# schematic_usb_multirs232.net
KiCad netlist of a schematic drawn in Altium Designer
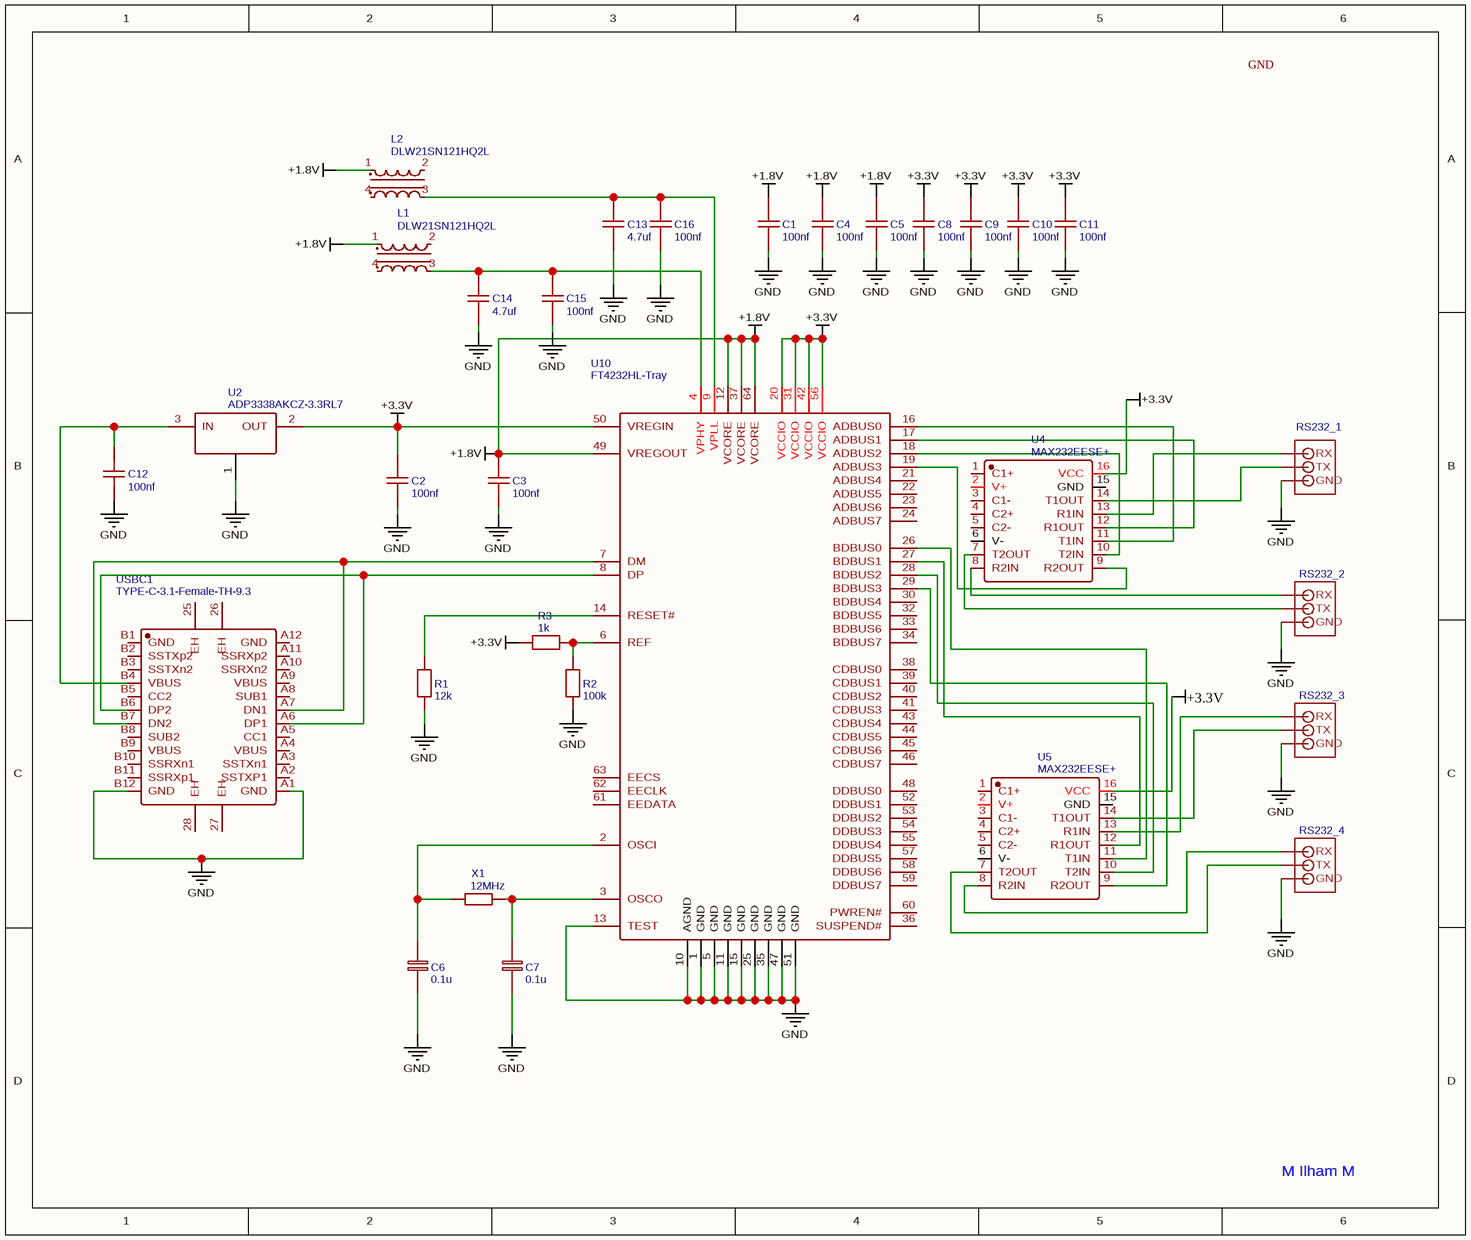
[diagram p0: schematic_usb_multirs232.schdoc]

(export (version "E")
  (design (tool "Eeschema 10.0.6"))
  (components
    (comp (ref "C1")
      (value "100nf")
      (fields (field (name "CONTRIBUTOR") "LCEDA_Lib"))
      (libsource (lib "altium-import") (part "root_3_100nf_"))
    )
    (comp (ref "C2")
      (value "100nf")
      (fields (field (name "CONTRIBUTOR") "LCEDA_Lib"))
      (libsource (lib "altium-import") (part "root_3_100nf_"))
    )
    (comp (ref "C3")
      (value "100nf")
      (fields (field (name "CONTRIBUTOR") "LCEDA_Lib"))
      (libsource (lib "altium-import") (part "root_3_100nf_"))
    )
    (comp (ref "C4")
      (value "100nf")
      (fields (field (name "CONTRIBUTOR") "LCEDA_Lib"))
      (libsource (lib "altium-import") (part "root_3_100nf_"))
    )
    (comp (ref "C5")
      (value "100nf")
      (fields (field (name "CONTRIBUTOR") "LCEDA_Lib"))
      (libsource (lib "altium-import") (part "root_3_100nf_"))
    )
    (comp (ref "C6")
      (value "0.1u")
      (fields (field (name "CONTRIBUTOR") "LCEDA_Lib"))
      (libsource (lib "altium-import") (part "root_3_0.1u_"))
    )
    (comp (ref "C7")
      (value "0.1u")
      (fields (field (name "CONTRIBUTOR") "LCEDA_Lib"))
      (libsource (lib "altium-import") (part "root_3_0.1u_"))
    )
    (comp (ref "C8")
      (value "100nf")
      (fields (field (name "CONTRIBUTOR") "LCEDA_Lib"))
      (libsource (lib "altium-import") (part "root_3_100nf_"))
    )
    (comp (ref "C9")
      (value "100nf")
      (fields (field (name "CONTRIBUTOR") "LCEDA_Lib"))
      (libsource (lib "altium-import") (part "root_3_100nf_"))
    )
    (comp (ref "C10")
      (value "100nf")
      (fields (field (name "CONTRIBUTOR") "LCEDA_Lib"))
      (libsource (lib "altium-import") (part "root_3_100nf_"))
    )
    (comp (ref "C11")
      (value "100nf")
      (fields (field (name "CONTRIBUTOR") "LCEDA_Lib"))
      (libsource (lib "altium-import") (part "root_3_100nf_"))
    )
    (comp (ref "C12")
      (value "100nf")
      (fields (field (name "CONTRIBUTOR") "LCEDA_Lib"))
      (libsource (lib "altium-import") (part "root_3_100nf_"))
    )
    (comp (ref "C13")
      (value "4.7uf")
      (fields (field (name "CONTRIBUTOR") "LCEDA_Lib"))
      (libsource (lib "altium-import") (part "root_3_4.7uf_"))
    )
    (comp (ref "C14")
      (value "4.7uf")
      (fields (field (name "CONTRIBUTOR") "LCEDA_Lib"))
      (libsource (lib "altium-import") (part "root_3_4.7uf_"))
    )
    (comp (ref "C15")
      (value "100nf")
      (fields (field (name "CONTRIBUTOR") "LCEDA_Lib"))
      (libsource (lib "altium-import") (part "root_3_100nf_"))
    )
    (comp (ref "C16")
      (value "100nf")
      (fields (field (name "CONTRIBUTOR") "LCEDA_Lib"))
      (libsource (lib "altium-import") (part "root_3_100nf_"))
    )
    (comp (ref "L1")
      (value "DLW21SN121HQ2L")
      (fields (field (name "MANUFACTURER") "muRata(村田)") (field (name "CONTRIBUTOR") "LCSC"))
      (libsource (lib "altium-import") (part "root_0_DLW21SN121HQ2L_"))
    )
    (comp (ref "L2")
      (value "DLW21SN121HQ2L")
      (fields (field (name "MANUFACTURER") "muRata(村田)") (field (name "CONTRIBUTOR") "LCSC"))
      (libsource (lib "altium-import") (part "root_0_DLW21SN121HQ2L_"))
    )
    (comp (ref "R1")
      (value "12k")
      (fields (field (name "CONTRIBUTOR") "LCEDA_Lib"))
      (libsource (lib "altium-import") (part "root_3_12k_"))
    )
    (comp (ref "R2")
      (value "100k")
      (fields (field (name "CONTRIBUTOR") "LCEDA_Lib"))
      (libsource (lib "altium-import") (part "root_3_100k_"))
    )
    (comp (ref "R3")
      (value "1k")
      (fields (field (name "CONTRIBUTOR") "LCEDA_Lib"))
      (libsource (lib "altium-import") (part "root_0_1k_"))
    )
    (comp (ref "RS232_1") (value "RX") (libsource (lib "altium-import") (part "root_0_RX_")))
    (comp (ref "U2")
      (value "ADP3338AKCZ-3.3RL7")
      (libsource (lib "altium-import") (part "root_0_ADP3338AKCZ-3.3RL7_"))
    )
    (comp (ref "U4")
      (value "MAX232EESE+")
      (fields (field (name "MANUFACTURER") "ADI(亚德诺)/MAXIM(美信)") (field (name "CONTRIBUTOR") "lcsc"))
      (libsource (lib "altium-import") (part "root_0_MAX232EESE+_"))
    )
    (comp (ref "U5")
      (value "MAX232EESE+")
      (fields (field (name "MANUFACTURER") "ADI(亚德诺)/MAXIM(美信)") (field (name "CONTRIBUTOR") "lcsc"))
      (libsource (lib "altium-import") (part "root_0_MAX232EESE+_"))
    )
    (comp (ref "U7") (value "RS232_2") (libsource (lib "altium-import") (part "root_0_RS232_2_")))
    (comp (ref "U8") (value "RS232_3") (libsource (lib "altium-import") (part "root_0_RS232_3_")))
    (comp (ref "U9") (value "RS232_4") (libsource (lib "altium-import") (part "root_0_RS232_4_")))
    (comp (ref "U10")
      (value "FT4232HL-Tray")
      (description "Quad High Speed USB To Multipurpose UARTMPSSE IC, 64-pin LQFP, Tray")
      (libsource (lib "altium-import") (part "root_0_FT4232HL-Tray_"))
    )
    (comp (ref "USBC1")
      (value "TYPE-C-3.1-Female-TH-9.3")
      (fields
        (field (name "MANUFACTURER") "精拓金")
        (field (name "MANUFACTURER PART") "918-418K2022Y40004")
        (field (name "CONTRIBUTOR") "LCSC")
      )
      (libsource (lib "altium-import") (part "root_0_TYPE-C-3.1-Female-TH-9.3_"))
    )
    (comp (ref "X1")
      (value "12MHz")
      (fields
        (field (name "MANUFACTURER") "CTS(西迪斯)")
        (field (name "MANUFACTURER PART") "ATS240CSM-1E")
        (field (name "CONTRIBUTOR") "LCSC")
      )
      (libsource (lib "altium-import") (part "root_0_12MHz_"))
    )
  )
  (nets
    (net (code "1") (name "+1.8V") (class "Default")
      (node (ref "C1") (pin "1") (pinfunction "1_1") (pintype "passive"))
      (node (ref "C3") (pin "1") (pinfunction "1_1") (pintype "passive"))
      (node (ref "C4") (pin "1") (pinfunction "1_1") (pintype "passive"))
      (node (ref "C5") (pin "1") (pinfunction "1_1") (pintype "passive"))
      (node (ref "L1") (pin "1") (pinfunction "1_1") (pintype "passive"))
      (node (ref "L2") (pin "1") (pinfunction "1_1") (pintype "passive"))
      (node (ref "U10") (pin "12") (pinfunction "VCORE_12") (pintype "passive"))
      (node (ref "U10") (pin "37") (pinfunction "VCORE_37") (pintype "passive"))
      (node (ref "U10") (pin "49") (pinfunction "VREGOUT_49") (pintype "passive"))
      (node (ref "U10") (pin "64") (pinfunction "VCORE_64") (pintype "passive"))
      (node (ref "U5") (pin "16") (pinfunction "VCC_16") (pintype "passive"))
    )
    (net (code "2") (name "+3.3V") (class "Default")
      (node (ref "C10") (pin "1") (pinfunction "1_1") (pintype "passive"))
      (node (ref "C11") (pin "1") (pinfunction "1_1") (pintype "passive"))
      (node (ref "C2") (pin "1") (pinfunction "1_1") (pintype "passive"))
      (node (ref "C8") (pin "1") (pinfunction "1_1") (pintype "passive"))
      (node (ref "C9") (pin "1") (pinfunction "1_1") (pintype "passive"))
      (node (ref "R3") (pin "1") (pinfunction "1_1") (pintype "passive"))
      (node (ref "U10") (pin "20") (pinfunction "VCCIO_20") (pintype "passive"))
      (node (ref "U10") (pin "31") (pinfunction "VCCIO_31") (pintype "passive"))
      (node (ref "U10") (pin "42") (pinfunction "VCCIO_42") (pintype "passive"))
      (node (ref "U10") (pin "50") (pinfunction "VREGIN_50") (pintype "passive"))
      (node (ref "U10") (pin "56") (pinfunction "VCCIO_56") (pintype "passive"))
      (node (ref "U2") (pin "2") (pinfunction "OUT_2") (pintype "passive"))
      (node (ref "U4") (pin "16") (pinfunction "VCC_16") (pintype "passive"))
    )
    (net (code "3") (name "GND") (class "Default")
      (node (ref "C1") (pin "2") (pinfunction "2_2") (pintype "passive"))
      (node (ref "C10") (pin "2") (pinfunction "2_2") (pintype "passive"))
      (node (ref "C11") (pin "2") (pinfunction "2_2") (pintype "passive"))
      (node (ref "C12") (pin "2") (pinfunction "2_2") (pintype "passive"))
      (node (ref "C13") (pin "2") (pinfunction "2_2") (pintype "passive"))
      (node (ref "C14") (pin "2") (pinfunction "2_2") (pintype "passive"))
      (node (ref "C15") (pin "2") (pinfunction "2_2") (pintype "passive"))
      (node (ref "C16") (pin "2") (pinfunction "2_2") (pintype "passive"))
      (node (ref "C2") (pin "2") (pinfunction "2_2") (pintype "passive"))
      (node (ref "C3") (pin "2") (pinfunction "2_2") (pintype "passive"))
      (node (ref "C4") (pin "2") (pinfunction "2_2") (pintype "passive"))
      (node (ref "C5") (pin "2") (pinfunction "2_2") (pintype "passive"))
      (node (ref "C6") (pin "2") (pinfunction "2_2") (pintype "passive"))
      (node (ref "C7") (pin "2") (pinfunction "2_2") (pintype "passive"))
      (node (ref "C8") (pin "2") (pinfunction "2_2") (pintype "passive"))
      (node (ref "C9") (pin "2") (pinfunction "2_2") (pintype "passive"))
      (node (ref "R1") (pin "2") (pinfunction "2_2") (pintype "passive"))
      (node (ref "R2") (pin "2") (pinfunction "2_2") (pintype "passive"))
      (node (ref "RS232_1") (pin "P3") (pinfunction "GND_P3") (pintype "passive"))
      (node (ref "U10") (pin "1") (pinfunction "GND_1") (pintype "passive"))
      (node (ref "U10") (pin "10") (pinfunction "AGND_10") (pintype "passive"))
      (node (ref "U10") (pin "11") (pinfunction "GND_11") (pintype "passive"))
      (node (ref "U10") (pin "13") (pinfunction "TEST_13") (pintype "passive"))
      (node (ref "U10") (pin "15") (pinfunction "GND_15") (pintype "passive"))
      (node (ref "U10") (pin "25") (pinfunction "GND_25") (pintype "passive"))
      (node (ref "U10") (pin "35") (pinfunction "GND_35") (pintype "passive"))
      (node (ref "U10") (pin "47") (pinfunction "GND_47") (pintype "passive"))
      (node (ref "U10") (pin "5") (pinfunction "GND_5") (pintype "passive"))
      (node (ref "U10") (pin "51") (pinfunction "GND_51") (pintype "passive"))
      (node (ref "U2") (pin "1") (pinfunction "GND_1") (pintype "passive"))
      (node (ref "U7") (pin "P3") (pinfunction "GND_P3") (pintype "passive"))
      (node (ref "U8") (pin "P3") (pinfunction "GND_P3") (pintype "passive"))
      (node (ref "U9") (pin "P3") (pinfunction "GND_P3") (pintype "passive"))
      (node (ref "USBC1") (pin "A1") (pinfunction "GND_A1") (pintype "passive"))
      (node (ref "USBC1") (pin "B12") (pinfunction "GND_B12") (pintype "passive"))
    )
    (net (code "4") (name "Net-(RS232_1-RX)") (class "Default")
      (node (ref "RS232_1") (pin "P1") (pinfunction "RX_P1") (pintype "passive"))
      (node (ref "U4") (pin "13") (pinfunction "R1IN_13") (pintype "passive"))
    )
    (net (code "5") (name "Net-(RS232_1-TX)") (class "Default")
      (node (ref "RS232_1") (pin "P2") (pinfunction "TX_P2") (pintype "passive"))
      (node (ref "U4") (pin "14") (pinfunction "T1OUT_14") (pintype "passive"))
    )
    (net (code "6") (name "Net-(U2-IN)") (class "Default")
      (node (ref "C12") (pin "1") (pinfunction "1_1") (pintype "passive"))
      (node (ref "U2") (pin "3") (pinfunction "IN_3") (pintype "passive"))
      (node (ref "USBC1") (pin "B4") (pinfunction "VBUS_B4") (pintype "passive"))
    )
    (net (code "7") (name "Net-(U4-R2IN)") (class "Default")
      (node (ref "U4") (pin "8") (pinfunction "R2IN_8") (pintype "passive"))
      (node (ref "U7") (pin "P1") (pinfunction "RX_P1") (pintype "passive"))
    )
    (net (code "8") (name "Net-(U4-T2OUT)") (class "Default")
      (node (ref "U4") (pin "7") (pinfunction "T2OUT_7") (pintype "passive"))
      (node (ref "U7") (pin "P2") (pinfunction "TX_P2") (pintype "passive"))
    )
    (net (code "9") (name "Net-(U5-R1IN)") (class "Default")
      (node (ref "U5") (pin "13") (pinfunction "R1IN_13") (pintype "passive"))
      (node (ref "U8") (pin "P1") (pinfunction "RX_P1") (pintype "passive"))
    )
    (net (code "10") (name "Net-(U5-R2IN)") (class "Default")
      (node (ref "U5") (pin "8") (pinfunction "R2IN_8") (pintype "passive"))
      (node (ref "U9") (pin "P1") (pinfunction "RX_P1") (pintype "passive"))
    )
    (net (code "11") (name "Net-(U5-T1OUT)") (class "Default")
      (node (ref "U5") (pin "14") (pinfunction "T1OUT_14") (pintype "passive"))
      (node (ref "U8") (pin "P2") (pinfunction "TX_P2") (pintype "passive"))
    )
    (net (code "12") (name "Net-(U5-T2OUT)") (class "Default")
      (node (ref "U5") (pin "7") (pinfunction "T2OUT_7") (pintype "passive"))
      (node (ref "U9") (pin "P2") (pinfunction "TX_P2") (pintype "passive"))
    )
    (net (code "13") (name "Net-(U10-ADBUS0)") (class "Default")
      (node (ref "U10") (pin "16") (pinfunction "ADBUS0_16") (pintype "passive"))
      (node (ref "U4") (pin "11") (pinfunction "T1IN_11") (pintype "passive"))
    )
    (net (code "14") (name "Net-(U10-ADBUS1)") (class "Default")
      (node (ref "U10") (pin "17") (pinfunction "ADBUS1_17") (pintype "passive"))
      (node (ref "U4") (pin "12") (pinfunction "R1OUT_12") (pintype "passive"))
    )
    (net (code "15") (name "Net-(U10-ADBUS2)") (class "Default")
      (node (ref "U10") (pin "18") (pinfunction "ADBUS2_18") (pintype "passive"))
      (node (ref "U4") (pin "10") (pinfunction "T2IN_10") (pintype "passive"))
    )
    (net (code "16") (name "Net-(U10-ADBUS3)") (class "Default")
      (node (ref "U10") (pin "19") (pinfunction "ADBUS3_19") (pintype "passive"))
      (node (ref "U4") (pin "9") (pinfunction "R2OUT_9") (pintype "passive"))
    )
    (net (code "17") (name "Net-(U10-BDBUS0)") (class "Default")
      (node (ref "U10") (pin "26") (pinfunction "BDBUS0_26") (pintype "passive"))
      (node (ref "U5") (pin "11") (pinfunction "T1IN_11") (pintype "passive"))
    )
    (net (code "18") (name "Net-(U10-BDBUS1)") (class "Default")
      (node (ref "U10") (pin "27") (pinfunction "BDBUS1_27") (pintype "passive"))
      (node (ref "U5") (pin "12") (pinfunction "R1OUT_12") (pintype "passive"))
    )
    (net (code "19") (name "Net-(U10-BDBUS2)") (class "Default")
      (node (ref "U10") (pin "28") (pinfunction "BDBUS2_28") (pintype "passive"))
      (node (ref "U5") (pin "10") (pinfunction "T2IN_10") (pintype "passive"))
    )
    (net (code "20") (name "Net-(U10-BDBUS3)") (class "Default")
      (node (ref "U10") (pin "29") (pinfunction "BDBUS3_29") (pintype "passive"))
      (node (ref "U5") (pin "9") (pinfunction "R2OUT_9") (pintype "passive"))
    )
    (net (code "21") (name "Net-(U10-DM)") (class "Default")
      (node (ref "U10") (pin "7") (pinfunction "DM_7") (pintype "passive"))
      (node (ref "USBC1") (pin "A7") (pinfunction "DN1_A7") (pintype "passive"))
      (node (ref "USBC1") (pin "B7") (pinfunction "DN2_B7") (pintype "passive"))
    )
    (net (code "22") (name "Net-(U10-DP)") (class "Default")
      (node (ref "U10") (pin "8") (pinfunction "DP_8") (pintype "passive"))
      (node (ref "USBC1") (pin "A6") (pinfunction "DP1_A6") (pintype "passive"))
      (node (ref "USBC1") (pin "B6") (pinfunction "DP2_B6") (pintype "passive"))
    )
    (net (code "23") (name "Net-(U10-OSCI)") (class "Default")
      (node (ref "C6") (pin "1") (pinfunction "1_1") (pintype "passive"))
      (node (ref "U10") (pin "2") (pinfunction "OSCI_2") (pintype "passive"))
      (node (ref "X1") (pin "1") (pinfunction "1_1") (pintype "passive"))
    )
    (net (code "24") (name "Net-(U10-OSCO)") (class "Default")
      (node (ref "C7") (pin "1") (pinfunction "1_1") (pintype "passive"))
      (node (ref "U10") (pin "3") (pinfunction "OSCO_3") (pintype "passive"))
      (node (ref "X1") (pin "2") (pinfunction "2_2") (pintype "passive"))
    )
    (net (code "25") (name "Net-(U10-REF)") (class "Default")
      (node (ref "R2") (pin "1") (pinfunction "1_1") (pintype "passive"))
      (node (ref "R3") (pin "2") (pinfunction "2_2") (pintype "passive"))
      (node (ref "U10") (pin "6") (pinfunction "REF_6") (pintype "passive"))
    )
    (net (code "26") (name "Net-(U10-RESET#)") (class "Default")
      (node (ref "R1") (pin "1") (pinfunction "1_1") (pintype "passive"))
      (node (ref "U10") (pin "14") (pinfunction "RESET#_14") (pintype "passive"))
    )
    (net (code "27") (name "Net-(U10-VPHY)") (class "Default")
      (node (ref "C14") (pin "1") (pinfunction "1_1") (pintype "passive"))
      (node (ref "C15") (pin "1") (pinfunction "1_1") (pintype "passive"))
      (node (ref "L1") (pin "3") (pinfunction "3_3") (pintype "passive"))
      (node (ref "U10") (pin "4") (pinfunction "VPHY_4") (pintype "passive"))
    )
    (net (code "28") (name "Net-(U10-VPLL)") (class "Default")
      (node (ref "C13") (pin "1") (pinfunction "1_1") (pintype "passive"))
      (node (ref "C16") (pin "1") (pinfunction "1_1") (pintype "passive"))
      (node (ref "L2") (pin "3") (pinfunction "3_3") (pintype "passive"))
      (node (ref "U10") (pin "9") (pinfunction "VPLL_9") (pintype "passive"))
    )
    (net (code "29") (name "unconnected-(L1-Pad2)") (class "Default")
      (node (ref "L1") (pin "2") (pinfunction "2_2") (pintype "passive"))
    )
    (net (code "30") (name "unconnected-(L1-Pad4)") (class "Default")
      (node (ref "L1") (pin "4") (pinfunction "4_4") (pintype "passive"))
    )
    (net (code "31") (name "unconnected-(L2-Pad2)") (class "Default")
      (node (ref "L2") (pin "2") (pinfunction "2_2") (pintype "passive"))
    )
    (net (code "32") (name "unconnected-(L2-Pad4)") (class "Default")
      (node (ref "L2") (pin "4") (pinfunction "4_4") (pintype "passive"))
    )
    (net (code "33") (name "unconnected-(U4-C1+-Pad1)") (class "Default")
      (node (ref "U4") (pin "1") (pinfunction "C1+_1") (pintype "passive"))
    )
    (net (code "34") (name "unconnected-(U4-C1--Pad3)") (class "Default")
      (node (ref "U4") (pin "3") (pinfunction "C1-_3") (pintype "passive"))
    )
    (net (code "35") (name "unconnected-(U4-C2+-Pad4)") (class "Default")
      (node (ref "U4") (pin "4") (pinfunction "C2+_4") (pintype "passive"))
    )
    (net (code "36") (name "unconnected-(U4-C2--Pad5)") (class "Default")
      (node (ref "U4") (pin "5") (pinfunction "C2-_5") (pintype "passive"))
    )
    (net (code "37") (name "unconnected-(U4-GND-Pad15)") (class "Default")
      (node (ref "U4") (pin "15") (pinfunction "GND_15") (pintype "passive"))
    )
    (net (code "38") (name "unconnected-(U4-V+-Pad2)") (class "Default")
      (node (ref "U4") (pin "2") (pinfunction "V+_2") (pintype "passive"))
    )
    (net (code "39") (name "unconnected-(U4-V--Pad6)") (class "Default")
      (node (ref "U4") (pin "6") (pinfunction "V-_6") (pintype "passive"))
    )
    (net (code "40") (name "unconnected-(U5-C1+-Pad1)") (class "Default")
      (node (ref "U5") (pin "1") (pinfunction "C1+_1") (pintype "passive"))
    )
    (net (code "41") (name "unconnected-(U5-C1--Pad3)") (class "Default")
      (node (ref "U5") (pin "3") (pinfunction "C1-_3") (pintype "passive"))
    )
    (net (code "42") (name "unconnected-(U5-C2+-Pad4)") (class "Default")
      (node (ref "U5") (pin "4") (pinfunction "C2+_4") (pintype "passive"))
    )
    (net (code "43") (name "unconnected-(U5-C2--Pad5)") (class "Default")
      (node (ref "U5") (pin "5") (pinfunction "C2-_5") (pintype "passive"))
    )
    (net (code "44") (name "unconnected-(U5-GND-Pad15)") (class "Default")
      (node (ref "U5") (pin "15") (pinfunction "GND_15") (pintype "passive"))
    )
    (net (code "45") (name "unconnected-(U5-V+-Pad2)") (class "Default")
      (node (ref "U5") (pin "2") (pinfunction "V+_2") (pintype "passive"))
    )
    (net (code "46") (name "unconnected-(U5-V--Pad6)") (class "Default")
      (node (ref "U5") (pin "6") (pinfunction "V-_6") (pintype "passive"))
    )
    (net (code "47") (name "unconnected-(U10-ADBUS4-Pad21)") (class "Default")
      (node (ref "U10") (pin "21") (pinfunction "ADBUS4_21") (pintype "passive"))
    )
    (net (code "48") (name "unconnected-(U10-ADBUS5-Pad22)") (class "Default")
      (node (ref "U10") (pin "22") (pinfunction "ADBUS5_22") (pintype "passive"))
    )
    (net (code "49") (name "unconnected-(U10-ADBUS6-Pad23)") (class "Default")
      (node (ref "U10") (pin "23") (pinfunction "ADBUS6_23") (pintype "passive"))
    )
    (net (code "50") (name "unconnected-(U10-ADBUS7-Pad24)") (class "Default")
      (node (ref "U10") (pin "24") (pinfunction "ADBUS7_24") (pintype "passive"))
    )
    (net (code "51") (name "unconnected-(U10-BDBUS4-Pad30)") (class "Default")
      (node (ref "U10") (pin "30") (pinfunction "BDBUS4_30") (pintype "passive"))
    )
    (net (code "52") (name "unconnected-(U10-BDBUS5-Pad32)") (class "Default")
      (node (ref "U10") (pin "32") (pinfunction "BDBUS5_32") (pintype "passive"))
    )
    (net (code "53") (name "unconnected-(U10-BDBUS6-Pad33)") (class "Default")
      (node (ref "U10") (pin "33") (pinfunction "BDBUS6_33") (pintype "passive"))
    )
    (net (code "54") (name "unconnected-(U10-BDBUS7-Pad34)") (class "Default")
      (node (ref "U10") (pin "34") (pinfunction "BDBUS7_34") (pintype "passive"))
    )
    (net (code "55") (name "unconnected-(U10-CDBUS0-Pad38)") (class "Default")
      (node (ref "U10") (pin "38") (pinfunction "CDBUS0_38") (pintype "passive"))
    )
    (net (code "56") (name "unconnected-(U10-CDBUS1-Pad39)") (class "Default")
      (node (ref "U10") (pin "39") (pinfunction "CDBUS1_39") (pintype "passive"))
    )
    (net (code "57") (name "unconnected-(U10-CDBUS2-Pad40)") (class "Default")
      (node (ref "U10") (pin "40") (pinfunction "CDBUS2_40") (pintype "passive"))
    )
    (net (code "58") (name "unconnected-(U10-CDBUS3-Pad41)") (class "Default")
      (node (ref "U10") (pin "41") (pinfunction "CDBUS3_41") (pintype "passive"))
    )
    (net (code "59") (name "unconnected-(U10-CDBUS4-Pad43)") (class "Default")
      (node (ref "U10") (pin "43") (pinfunction "CDBUS4_43") (pintype "passive"))
    )
    (net (code "60") (name "unconnected-(U10-CDBUS5-Pad44)") (class "Default")
      (node (ref "U10") (pin "44") (pinfunction "CDBUS5_44") (pintype "passive"))
    )
    (net (code "61") (name "unconnected-(U10-CDBUS6-Pad45)") (class "Default")
      (node (ref "U10") (pin "45") (pinfunction "CDBUS6_45") (pintype "passive"))
    )
    (net (code "62") (name "unconnected-(U10-CDBUS7-Pad46)") (class "Default")
      (node (ref "U10") (pin "46") (pinfunction "CDBUS7_46") (pintype "passive"))
    )
    (net (code "63") (name "unconnected-(U10-DDBUS0-Pad48)") (class "Default")
      (node (ref "U10") (pin "48") (pinfunction "DDBUS0_48") (pintype "passive"))
    )
    (net (code "64") (name "unconnected-(U10-DDBUS1-Pad52)") (class "Default")
      (node (ref "U10") (pin "52") (pinfunction "DDBUS1_52") (pintype "passive"))
    )
    (net (code "65") (name "unconnected-(U10-DDBUS2-Pad53)") (class "Default")
      (node (ref "U10") (pin "53") (pinfunction "DDBUS2_53") (pintype "passive"))
    )
    (net (code "66") (name "unconnected-(U10-DDBUS3-Pad54)") (class "Default")
      (node (ref "U10") (pin "54") (pinfunction "DDBUS3_54") (pintype "passive"))
    )
    (net (code "67") (name "unconnected-(U10-DDBUS4-Pad55)") (class "Default")
      (node (ref "U10") (pin "55") (pinfunction "DDBUS4_55") (pintype "passive"))
    )
    (net (code "68") (name "unconnected-(U10-DDBUS5-Pad57)") (class "Default")
      (node (ref "U10") (pin "57") (pinfunction "DDBUS5_57") (pintype "passive"))
    )
    (net (code "69") (name "unconnected-(U10-DDBUS6-Pad58)") (class "Default")
      (node (ref "U10") (pin "58") (pinfunction "DDBUS6_58") (pintype "passive"))
    )
    (net (code "70") (name "unconnected-(U10-DDBUS7-Pad59)") (class "Default")
      (node (ref "U10") (pin "59") (pinfunction "DDBUS7_59") (pintype "passive"))
    )
    (net (code "71") (name "unconnected-(U10-EECLK-Pad62)") (class "Default")
      (node (ref "U10") (pin "62") (pinfunction "EECLK_62") (pintype "passive"))
    )
    (net (code "72") (name "unconnected-(U10-EECS-Pad63)") (class "Default")
      (node (ref "U10") (pin "63") (pinfunction "EECS_63") (pintype "passive"))
    )
    (net (code "73") (name "unconnected-(U10-EEDATA-Pad61)") (class "Default")
      (node (ref "U10") (pin "61") (pinfunction "EEDATA_61") (pintype "passive"))
    )
    (net (code "74") (name "unconnected-(U10-PWREN#-Pad60)") (class "Default")
      (node (ref "U10") (pin "60") (pinfunction "PWREN#_60") (pintype "passive"))
    )
    (net (code "75") (name "unconnected-(U10-SUSPEND#-Pad36)") (class "Default")
      (node (ref "U10") (pin "36") (pinfunction "SUSPEND#_36") (pintype "passive"))
    )
    (net (code "76") (name "unconnected-(USBC1-CC1-PadA5)") (class "Default")
      (node (ref "USBC1") (pin "A5") (pinfunction "CC1_A5") (pintype "passive"))
    )
    (net (code "77") (name "unconnected-(USBC1-CC2-PadB5)") (class "Default")
      (node (ref "USBC1") (pin "B5") (pinfunction "CC2_B5") (pintype "passive"))
    )
    (net (code "78") (name "unconnected-(USBC1-EH-Pad25)") (class "Default")
      (node (ref "USBC1") (pin "25") (pinfunction "EH_25") (pintype "passive"))
    )
    (net (code "79") (name "unconnected-(USBC1-EH-Pad26)") (class "Default")
      (node (ref "USBC1") (pin "26") (pinfunction "EH_26") (pintype "passive"))
    )
    (net (code "80") (name "unconnected-(USBC1-EH-Pad27)") (class "Default")
      (node (ref "USBC1") (pin "27") (pinfunction "EH_27") (pintype "passive"))
    )
    (net (code "81") (name "unconnected-(USBC1-EH-Pad28)") (class "Default")
      (node (ref "USBC1") (pin "28") (pinfunction "EH_28") (pintype "passive"))
    )
    (net (code "82") (name "unconnected-(USBC1-GND-PadA12)") (class "Default")
      (node (ref "USBC1") (pin "A12") (pinfunction "GND_A12") (pintype "passive"))
    )
    (net (code "83") (name "unconnected-(USBC1-GND-PadB1)") (class "Default")
      (node (ref "USBC1") (pin "B1") (pinfunction "GND_B1") (pintype "passive"))
    )
    (net (code "84") (name "unconnected-(USBC1-SSRXn1-PadB10)") (class "Default")
      (node (ref "USBC1") (pin "B10") (pinfunction "SSRXn1_B10") (pintype "passive"))
    )
    (net (code "85") (name "unconnected-(USBC1-SSRXn2-PadA10)") (class "Default")
      (node (ref "USBC1") (pin "A10") (pinfunction "SSRXn2_A10") (pintype "passive"))
    )
    (net (code "86") (name "unconnected-(USBC1-SSRXp1-PadB11)") (class "Default")
      (node (ref "USBC1") (pin "B11") (pinfunction "SSRXp1_B11") (pintype "passive"))
    )
    (net (code "87") (name "unconnected-(USBC1-SSRXp2-PadA11)") (class "Default")
      (node (ref "USBC1") (pin "A11") (pinfunction "SSRXp2_A11") (pintype "passive"))
    )
    (net (code "88") (name "unconnected-(USBC1-SSTXP1-PadA2)") (class "Default")
      (node (ref "USBC1") (pin "A2") (pinfunction "SSTXP1_A2") (pintype "passive"))
    )
    (net (code "89") (name "unconnected-(USBC1-SSTXn1-PadA3)") (class "Default")
      (node (ref "USBC1") (pin "A3") (pinfunction "SSTXn1_A3") (pintype "passive"))
    )
    (net (code "90") (name "unconnected-(USBC1-SSTXn2-PadB3)") (class "Default")
      (node (ref "USBC1") (pin "B3") (pinfunction "SSTXn2_B3") (pintype "passive"))
    )
    (net (code "91") (name "unconnected-(USBC1-SSTXp2-PadB2)") (class "Default")
      (node (ref "USBC1") (pin "B2") (pinfunction "SSTXp2_B2") (pintype "passive"))
    )
    (net (code "92") (name "unconnected-(USBC1-SUB1-PadA8)") (class "Default")
      (node (ref "USBC1") (pin "A8") (pinfunction "SUB1_A8") (pintype "passive"))
    )
    (net (code "93") (name "unconnected-(USBC1-SUB2-PadB8)") (class "Default")
      (node (ref "USBC1") (pin "B8") (pinfunction "SUB2_B8") (pintype "passive"))
    )
    (net (code "94") (name "unconnected-(USBC1-VBUS-PadA4)") (class "Default")
      (node (ref "USBC1") (pin "A4") (pinfunction "VBUS_A4") (pintype "passive"))
    )
    (net (code "95") (name "unconnected-(USBC1-VBUS-PadA9)") (class "Default")
      (node (ref "USBC1") (pin "A9") (pinfunction "VBUS_A9") (pintype "passive"))
    )
    (net (code "96") (name "unconnected-(USBC1-VBUS-PadB9)") (class "Default")
      (node (ref "USBC1") (pin "B9") (pinfunction "VBUS_B9") (pintype "passive"))
    )
  )
)
